# autism_ray_xaio.net
KiCad netlist of a schematic drawn in EAGLE
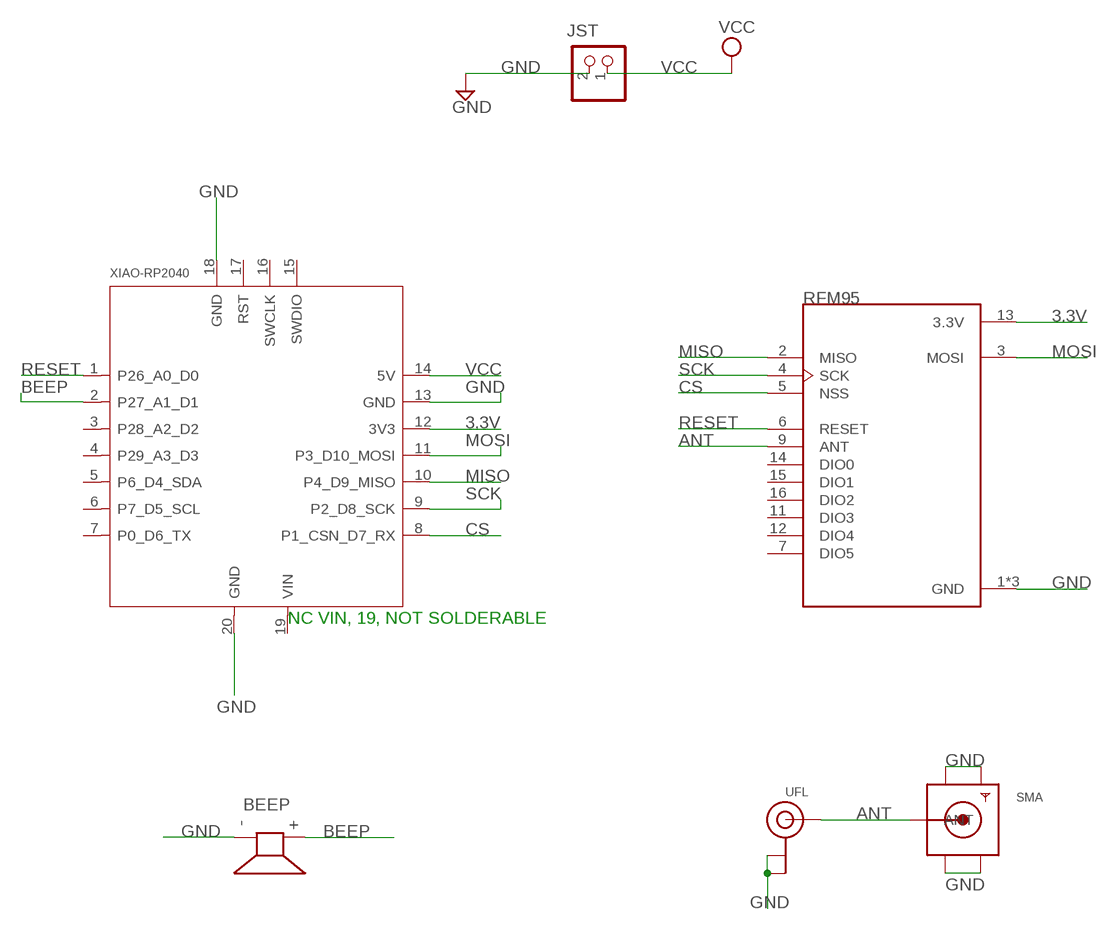
[diagram p0: schematic, sheet 1]

(export (version "E")
  (design (tool "Eeschema 10.0.6"))
  (components
    (comp (ref "BEEP")
      (value "AI-1223-TWT-12V-R")
      (footprint "eagle-import:XDCR_AI-1223-TWT-12V-R")
      (fields (field (name "MF") "PUI Audio,"))
      (libsource (lib "eagle-import") (part "AI-1223-TWT-12V-R"))
    )
    (comp (ref "JST")
      (value "JST_2PIN-SMT-RA")
      (footprint "eagle-import:JST-PH-2-SMT-RA")
      (libsource (lib "eagle-import") (part "JST_2PIN-SMT-RA"))
    )
    (comp (ref "RFM95")
      (value "RFM95W-915S2")
      (footprint "eagle-import:XCVR_RFM95W-915S2")
      (fields (field (name "MF") "RF Solutions"))
      (libsource (lib "eagle-import") (part "RFM95W-915S2"))
    )
    (comp (ref "SMA")
      (value "SMACONNECTOR_EDGE")
      (footprint "eagle-import:SMA_EDGELAUNCH")
      (libsource (lib "eagle-import") (part "SMACONNECTOR_EDGE"))
    )
    (comp (ref "UFL")
      (value "ANTENNA_U.FL")
      (footprint "eagle-import:U.FL")
      (libsource (lib "eagle-import") (part "ANTENNA_U.FL"))
    )
    (comp (ref "XIAO-RP2040")
      (value "XIAO-RP2040")
      (footprint "eagle-import:XIAO-SAMD21_RP2040-MODULE14P-2.54-21X17.8MM")
      (libsource (lib "eagle-import") (part "XIAO-RP2040"))
    )
  )
  (nets
    (net (code "1") (name "/3.3V") (class "Default")
      (node (ref "RFM95") (pin "13") (pinfunction "3.3V_13") (pintype "power_in"))
      (node (ref "XIAO-RP2040") (pin "12") (pinfunction "3V3_12") (pintype "bidirectional"))
    )
    (net (code "2") (name "/ANT") (class "Default")
      (node (ref "RFM95") (pin "9") (pinfunction "ANT_9") (pintype "bidirectional"))
      (node (ref "SMA") (pin "P") (pinfunction "ANT_P") (pintype "bidirectional"))
      (node (ref "UFL") (pin "3") (pinfunction "SIGNAL_3") (pintype "passive"))
    )
    (net (code "3") (name "/BEEP") (class "Default")
      (node (ref "BEEP") (pin "P") (pinfunction "+_P") (pintype "passive"))
      (node (ref "XIAO-RP2040") (pin "2") (pinfunction "P27_A1_D1_2") (pintype "bidirectional"))
    )
    (net (code "4") (name "/CS") (class "Default")
      (node (ref "RFM95") (pin "5") (pinfunction "NSS_5") (pintype "input"))
      (node (ref "XIAO-RP2040") (pin "8") (pinfunction "P1_CSN_D7_RX_8") (pintype "bidirectional"))
    )
    (net (code "5") (name "/MISO") (class "Default")
      (node (ref "RFM95") (pin "2") (pinfunction "MISO_2") (pintype "input"))
      (node (ref "XIAO-RP2040") (pin "10") (pinfunction "P4_D9_MISO_10") (pintype "bidirectional"))
    )
    (net (code "6") (name "/MOSI") (class "Default")
      (node (ref "RFM95") (pin "3") (pinfunction "MOSI_3") (pintype "output"))
      (node (ref "XIAO-RP2040") (pin "11") (pinfunction "P3_D10_MOSI_11") (pintype "bidirectional"))
    )
    (net (code "7") (name "/RESET") (class "Default")
      (node (ref "RFM95") (pin "6") (pinfunction "RESET_6") (pintype "bidirectional"))
      (node (ref "XIAO-RP2040") (pin "1") (pinfunction "P26_A0_D0_1") (pintype "bidirectional"))
    )
    (net (code "8") (name "/SCK") (class "Default")
      (node (ref "RFM95") (pin "4") (pinfunction "SCK_4") (pintype "input"))
      (node (ref "XIAO-RP2040") (pin "9") (pinfunction "P2_D8_SCK_9") (pintype "bidirectional"))
    )
    (net (code "9") (name "GND") (class "Default")
      (node (ref "BEEP") (pin "N") (pinfunction "-_N") (pintype "passive"))
      (node (ref "JST") (pin "2") (pinfunction "1_2") (pintype "passive"))
      (node (ref "RFM95") (pin "1") (pinfunction "GND_1") (pintype "power_in"))
      (node (ref "RFM95") (pin "10") (pinfunction "GND_10") (pintype "power_in"))
      (node (ref "RFM95") (pin "8") (pinfunction "GND_8") (pintype "power_in"))
      (node (ref "SMA") (pin "GND@1") (pinfunction "GND4_GND@1") (pintype "power_in"))
      (node (ref "SMA") (pin "GND@2") (pinfunction "GND3_GND@2") (pintype "power_in"))
      (node (ref "SMA") (pin "GND@3") (pinfunction "GND2_GND@3") (pintype "power_in"))
      (node (ref "SMA") (pin "GND@4") (pinfunction "GND1_GND@4") (pintype "power_in"))
      (node (ref "UFL") (pin "1") (pinfunction "GND_1") (pintype "passive"))
      (node (ref "UFL") (pin "2") (pinfunction "GND_2") (pintype "passive"))
      (node (ref "XIAO-RP2040") (pin "13") (pinfunction "GND_13") (pintype "bidirectional"))
      (node (ref "XIAO-RP2040") (pin "18") (pinfunction "GND_18") (pintype "bidirectional"))
      (node (ref "XIAO-RP2040") (pin "20") (pinfunction "GND_20") (pintype "bidirectional"))
    )
    (net (code "10") (name "VCC") (class "Default")
      (node (ref "JST") (pin "1") (pinfunction "2_1") (pintype "passive"))
      (node (ref "XIAO-RP2040") (pin "14") (pinfunction "5V_14") (pintype "bidirectional"))
    )
    (net (code "11") (name "unconnected-(RFM95-DIO0-Pad14)") (class "Default")
      (node (ref "RFM95") (pin "14") (pinfunction "DIO0_14") (pintype "bidirectional"))
    )
    (net (code "12") (name "unconnected-(RFM95-DIO1-Pad15)") (class "Default")
      (node (ref "RFM95") (pin "15") (pinfunction "DIO1_15") (pintype "bidirectional"))
    )
    (net (code "13") (name "unconnected-(RFM95-DIO2-Pad16)") (class "Default")
      (node (ref "RFM95") (pin "16") (pinfunction "DIO2_16") (pintype "bidirectional"))
    )
    (net (code "14") (name "unconnected-(RFM95-DIO3-Pad11)") (class "Default")
      (node (ref "RFM95") (pin "11") (pinfunction "DIO3_11") (pintype "bidirectional"))
    )
    (net (code "15") (name "unconnected-(RFM95-DIO4-Pad12)") (class "Default")
      (node (ref "RFM95") (pin "12") (pinfunction "DIO4_12") (pintype "bidirectional"))
    )
    (net (code "16") (name "unconnected-(RFM95-DIO5-Pad7)") (class "Default")
      (node (ref "RFM95") (pin "7") (pinfunction "DIO5_7") (pintype "bidirectional"))
    )
    (net (code "17") (name "unconnected-(XIAO-RP2040-P0_D6_TX-Pad7)") (class "Default")
      (node (ref "XIAO-RP2040") (pin "7") (pinfunction "P0_D6_TX_7") (pintype "bidirectional"))
    )
    (net (code "18") (name "unconnected-(XIAO-RP2040-P6_D4_SDA-Pad5)") (class "Default")
      (node (ref "XIAO-RP2040") (pin "5") (pinfunction "P6_D4_SDA_5") (pintype "bidirectional"))
    )
    (net (code "19") (name "unconnected-(XIAO-RP2040-P7_D5_SCL-Pad6)") (class "Default")
      (node (ref "XIAO-RP2040") (pin "6") (pinfunction "P7_D5_SCL_6") (pintype "bidirectional"))
    )
    (net (code "20") (name "unconnected-(XIAO-RP2040-P28_A2_D2-Pad3)") (class "Default")
      (node (ref "XIAO-RP2040") (pin "3") (pinfunction "P28_A2_D2_3") (pintype "bidirectional"))
    )
    (net (code "21") (name "unconnected-(XIAO-RP2040-P29_A3_D3-Pad4)") (class "Default")
      (node (ref "XIAO-RP2040") (pin "4") (pinfunction "P29_A3_D3_4") (pintype "bidirectional"))
    )
    (net (code "22") (name "unconnected-(XIAO-RP2040-RST-Pad17)") (class "Default")
      (node (ref "XIAO-RP2040") (pin "17") (pinfunction "RST_17") (pintype "bidirectional"))
    )
    (net (code "23") (name "unconnected-(XIAO-RP2040-SWCLK-Pad16)") (class "Default")
      (node (ref "XIAO-RP2040") (pin "16") (pinfunction "SWCLK_16") (pintype "bidirectional"))
    )
    (net (code "24") (name "unconnected-(XIAO-RP2040-SWDIO-Pad15)") (class "Default")
      (node (ref "XIAO-RP2040") (pin "15") (pinfunction "SWDIO_15") (pintype "bidirectional"))
    )
    (net (code "25") (name "unconnected-(XIAO-RP2040-VIN-Pad19)") (class "Default")
      (node (ref "XIAO-RP2040") (pin "19") (pinfunction "VIN_19") (pintype "bidirectional"))
    )
  )
)
